# Beacons.net
KiCad netlist of a schematic drawn in Altium Designer
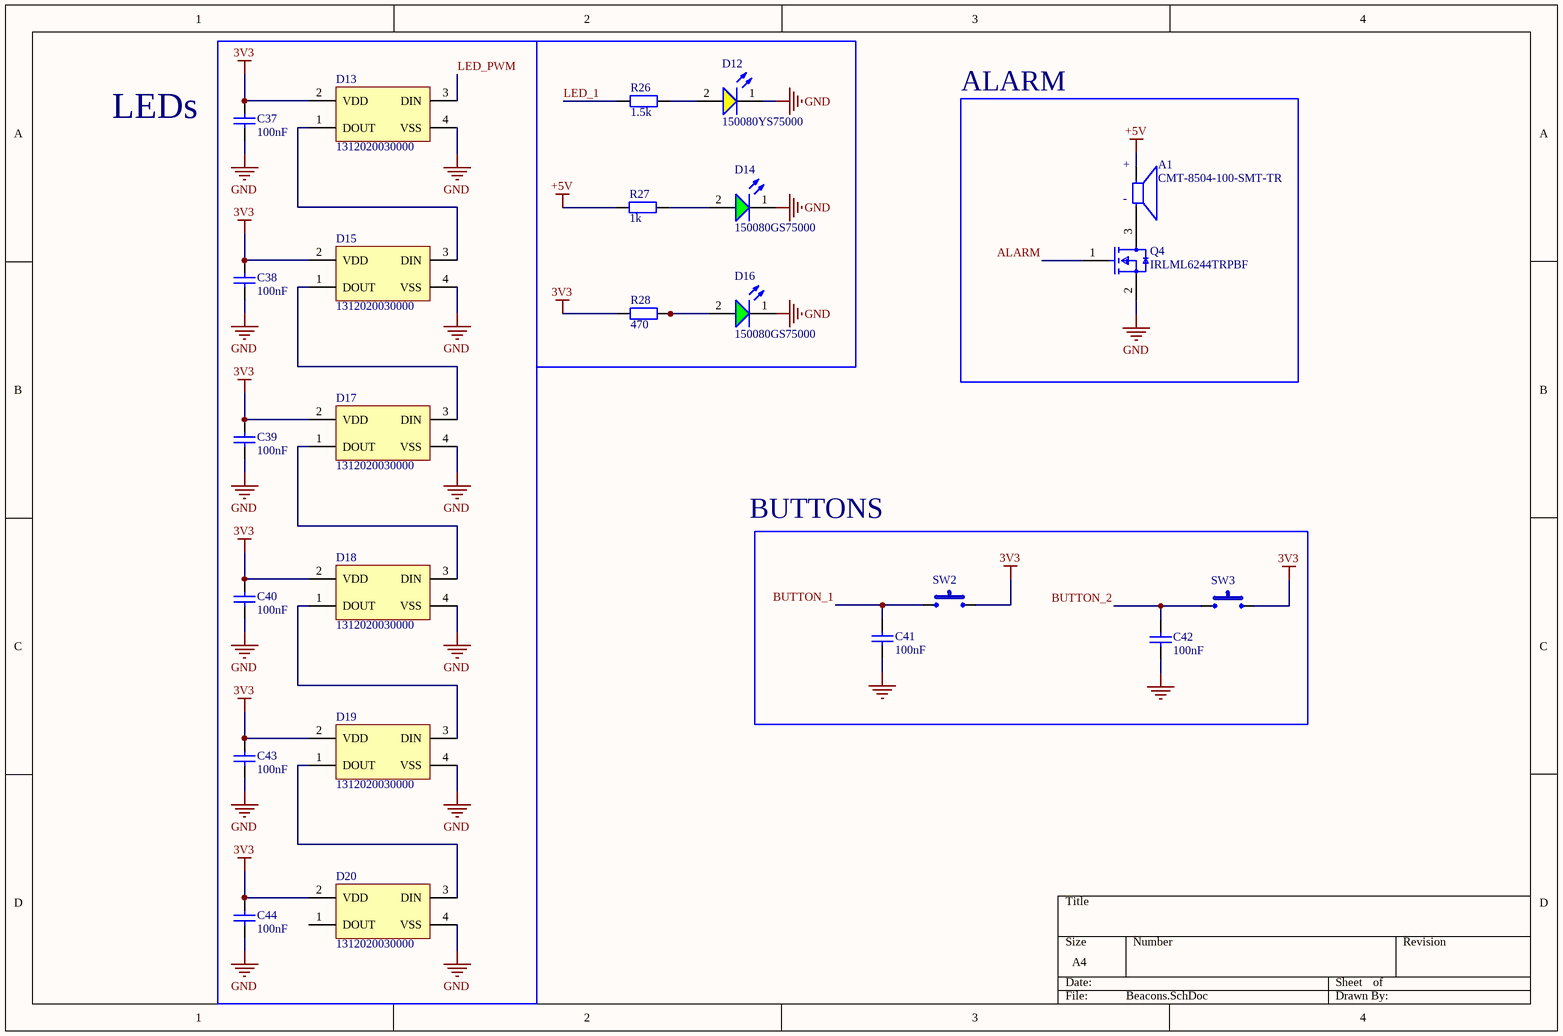
[diagram p0: Beacons.SchDoc]

(export (version "E")
  (design (tool "Eeschema 10.0.6"))
  (components
    (comp (ref "A1")
      (value "CMT-8504-100-SMT-TR")
      (footprint "CMT-8504-100-SMT-TR-Footprint-1")
      (description "Alarm")
      (libsource (lib "LEEM UPM") (part "CMT-8504-100"))
    )
    (comp (ref "C37")
      (value "100nF")
      (footprint "WCAP-CSGP_0603_L1.6W0.8H0.8_Reflow")
      (description "WCAP-CSGP Multilayer Ceramic Chip Capacitor, General Purpose, size 0603, X7R, 100nF, 25VDC")
      (fields
        (field (name "MANUFACTURER") "Wurth Elektronik")
        (field (name "MANUFACTURER PART NUMBER") "885012206071")
      )
      (libsource (lib "LEEM UPM") (part "885012209047R"))
    )
    (comp (ref "C38")
      (value "100nF")
      (footprint "WCAP-CSGP_0603_L1.6W0.8H0.8_Reflow")
      (description "WCAP-CSGP Multilayer Ceramic Chip Capacitor, General Purpose, size 0603, X7R, 100nF, 25VDC")
      (fields
        (field (name "MANUFACTURER") "Wurth Elektronik")
        (field (name "MANUFACTURER PART NUMBER") "885012206071")
      )
      (libsource (lib "LEEM UPM") (part "885012209047R"))
    )
    (comp (ref "C39")
      (value "100nF")
      (footprint "WCAP-CSGP_0603_L1.6W0.8H0.8_Reflow")
      (description "WCAP-CSGP Multilayer Ceramic Chip Capacitor, General Purpose, size 0603, X7R, 100nF, 25VDC")
      (fields
        (field (name "MANUFACTURER") "Wurth Elektronik")
        (field (name "MANUFACTURER PART NUMBER") "885012206071")
      )
      (libsource (lib "LEEM UPM") (part "885012209047R"))
    )
    (comp (ref "C40")
      (value "100nF")
      (footprint "WCAP-CSGP_0603_L1.6W0.8H0.8_Reflow")
      (description "WCAP-CSGP Multilayer Ceramic Chip Capacitor, General Purpose, size 0603, X7R, 100nF, 25VDC")
      (fields
        (field (name "MANUFACTURER") "Wurth Elektronik")
        (field (name "MANUFACTURER PART NUMBER") "885012206071")
      )
      (libsource (lib "LEEM UPM") (part "885012209047R"))
    )
    (comp (ref "C41")
      (value "100nF")
      (footprint "WCAP-CSGP_0603_L1.6W0.8H0.8_Reflow")
      (description "WCAP-CSGP Multilayer Ceramic Chip Capacitor, General Purpose, size 0603, X7R, 100nF, 25VDC")
      (fields
        (field (name "MANUFACTURER") "Wurth Elektronik")
        (field (name "MANUFACTURER PART NUMBER") "885012206071")
      )
      (libsource (lib "LEEM UPM") (part "885012209047R"))
    )
    (comp (ref "C42")
      (value "100nF")
      (footprint "WCAP-CSGP_0603_L1.6W0.8H0.8_Reflow")
      (description "WCAP-CSGP Multilayer Ceramic Chip Capacitor, General Purpose, size 0603, X7R, 100nF, 25VDC")
      (fields
        (field (name "MANUFACTURER") "Wurth Elektronik")
        (field (name "MANUFACTURER PART NUMBER") "885012206071")
      )
      (libsource (lib "LEEM UPM") (part "885012209047R"))
    )
    (comp (ref "C43")
      (value "100nF")
      (footprint "WCAP-CSGP_0603_L1.6W0.8H0.8_Reflow")
      (description "WCAP-CSGP Multilayer Ceramic Chip Capacitor, General Purpose, size 0603, X7R, 100nF, 25VDC")
      (fields
        (field (name "MANUFACTURER") "Wurth Elektronik")
        (field (name "MANUFACTURER PART NUMBER") "885012206071")
      )
      (libsource (lib "LEEM UPM") (part "885012209047R"))
    )
    (comp (ref "C44")
      (value "100nF")
      (footprint "WCAP-CSGP_0603_L1.6W0.8H0.8_Reflow")
      (description "WCAP-CSGP Multilayer Ceramic Chip Capacitor, General Purpose, size 0603, X7R, 100nF, 25VDC")
      (fields
        (field (name "MANUFACTURER") "Wurth Elektronik")
        (field (name "MANUFACTURER PART NUMBER") "885012206071")
      )
      (libsource (lib "LEEM UPM") (part "885012209047R"))
    )
    (comp (ref "D12")
      (value "150080YS75000")
      (footprint "WL-SMCW_0805_150080xx75000")
      (description "WL-SMCW Mono-color Chip LED Waterclear, SMT, size 0805, Yellow, 2V, 140°")
      (fields (field (name "MANUFACTURER") "Wurth Elektronik"))
      (libsource (lib "LEEM UPM") (part "150120YS87000"))
    )
    (comp (ref "D13")
      (value "1312020030000")
      (footprint "1312020030000")
      (description "WL-ICLED Integrated Controller within LED, Chip LED 2020, 5.5mA")
      (fields (field (name "MANUFACTURER") "Wurth Elektronik"))
      (libsource (lib "LEEM UPM") (part "1312020030000"))
    )
    (comp (ref "D14")
      (value "150080GS75000")
      (footprint "WL-SMCW_0805_150080xx75000")
      (description "WL-SMCW Mono-color Chip LED Waterclear, SMT, size 0805, Green, 3.2V, 140°")
      (fields (field (name "MANUFACTURER") "Wurth Elektronik"))
      (libsource (lib "LEEM UPM") (part "150120VS87000"))
    )
    (comp (ref "D15")
      (value "1312020030000")
      (footprint "1312020030000")
      (description "WL-ICLED Integrated Controller within LED, Chip LED 2020, 5.5mA")
      (fields (field (name "MANUFACTURER") "Wurth Elektronik"))
      (libsource (lib "LEEM UPM") (part "1312020030000"))
    )
    (comp (ref "D16")
      (value "150080GS75000")
      (footprint "WL-SMCW_0805_150080xx75000")
      (description "WURTH ELEKTRONIK - 150080GS75000 - LED, Green, SMD, 0805, 30 mA, 3.2 V, 520 nm")
      (libsource (lib "Altium Content Vault") (part "LED_Green_2A-1K"))
    )
    (comp (ref "D17")
      (value "1312020030000")
      (footprint "1312020030000")
      (description "WL-ICLED Integrated Controller within LED, Chip LED 2020, 5.5mA")
      (fields (field (name "MANUFACTURER") "Wurth Elektronik"))
      (libsource (lib "LEEM UPM") (part "1312020030000"))
    )
    (comp (ref "D18")
      (value "1312020030000")
      (footprint "1312020030000")
      (description "WL-ICLED Integrated Controller within LED, Chip LED 2020, 5.5mA")
      (fields (field (name "MANUFACTURER") "Wurth Elektronik"))
      (libsource (lib "LEEM UPM") (part "1312020030000"))
    )
    (comp (ref "D19")
      (value "1312020030000")
      (footprint "1312020030000")
      (description "WL-ICLED Integrated Controller within LED, Chip LED 2020, 5.5mA")
      (fields (field (name "MANUFACTURER") "Wurth Elektronik"))
      (libsource (lib "LEEM UPM") (part "1312020030000"))
    )
    (comp (ref "D20")
      (value "1312020030000")
      (footprint "1312020030000")
      (description "WL-ICLED Integrated Controller within LED, Chip LED 2020, 5.5mA")
      (fields (field (name "MANUFACTURER") "Wurth Elektronik"))
      (libsource (lib "LEEM UPM") (part "1312020030000"))
    )
    (comp (ref "Q4")
      (value "IRLML6244TRPBF")
      (footprint "FP-Micro3-IPC_C")
      (libsource (lib "LEEM UPM") (part "3b9c635fedb024a5347a57b145af9cc"))
    )
    (comp (ref "R26")
      (value "1.5k")
      (footprint "WRIS-RSKS_0603_Reflow")
      (description "WRIS-RSKS Thick Film Resistor, size 0603, 1500Ohm, 100mW")
      (fields
        (field (name "MANUFACTURER") "Wurth Elektronik")
        (field (name "MANUFACTURER PART NUMBER") "560112116038")
      )
      (libsource (lib "LEEM UPM") (part "560112140010"))
    )
    (comp (ref "R27")
      (value "1k")
      (footprint "WRIS-RSKS_0603_Reflow")
      (description "WRIS-RSKS Thick Film Resistor, size 0603, 1000Ohm, 100mW")
      (fields
        (field (name "MANUFACTURER PART NUMBER") "560112116014")
        (field (name "MANUFACTURER") "Wurth Elektronik")
      )
      (libsource (lib "LEEM UPM") (part "560112140010"))
    )
    (comp (ref "R28")
      (value "470")
      (footprint "WRIS-RSKS_0603_Reflow")
      (description "WRIS-RSKS Thick Film Resistor, size 0603, 470Ohm, 100mW")
      (fields
        (field (name "MANUFACTURER") "Wurth Elektronik")
        (field (name "MANUFACTURER PART NUMBER") "560112116067")
      )
      (libsource (lib "") (part "560112140010_1"))
    )
    (comp (ref "SW2")
      (value "PTS815SJM250SMTRLFS")
      (footprint "PTS815SJM250SMTRLFS-Footprint-1")
      (libsource (lib "LEEM UPM") (part "PTS815S"))
    )
    (comp (ref "SW3")
      (value "PTS815SJM250SMTRLFS")
      (footprint "PTS815SJM250SMTRLFS-Footprint-1")
      (libsource (lib "LEEM UPM") (part "PTS815S"))
    )
  )
  (nets
    (net (code "1") (name "+5V") (class "Default")
      (node (ref "A1") (pin "P") (pinfunction "P_P") (pintype "passive"))
      (node (ref "R27") (pin "1") (pinfunction "1_1") (pintype "passive"))
    )
    (net (code "2") (name "/ALARM") (class "Default")
      (node (ref "Q4") (pin "1") (pinfunction "G_1") (pintype "passive"))
    )
    (net (code "3") (name "/BUTTON_1") (class "Default")
      (node (ref "C41") (pin "2") (pinfunction "2_2") (pintype "passive"))
      (node (ref "SW2") (pin "1") (pinfunction "1_1") (pintype "passive"))
    )
    (net (code "4") (name "/BUTTON_2") (class "Default")
      (node (ref "C42") (pin "2") (pinfunction "2_2") (pintype "passive"))
      (node (ref "SW3") (pin "1") (pinfunction "1_1") (pintype "passive"))
    )
    (net (code "5") (name "/LED_1") (class "Default")
      (node (ref "R26") (pin "1") (pinfunction "1_1") (pintype "passive"))
    )
    (net (code "6") (name "/LED_PWM") (class "Default")
      (node (ref "D13") (pin "3") (pinfunction "DIN_3") (pintype "passive"))
    )
    (net (code "7") (name "3V3") (class "Default")
      (node (ref "C37") (pin "2") (pinfunction "2_2") (pintype "passive"))
      (node (ref "C38") (pin "2") (pinfunction "2_2") (pintype "passive"))
      (node (ref "C39") (pin "2") (pinfunction "2_2") (pintype "passive"))
      (node (ref "C40") (pin "2") (pinfunction "2_2") (pintype "passive"))
      (node (ref "C43") (pin "2") (pinfunction "2_2") (pintype "passive"))
      (node (ref "C44") (pin "2") (pinfunction "2_2") (pintype "passive"))
      (node (ref "D13") (pin "2") (pinfunction "VDD_2") (pintype "passive"))
      (node (ref "D15") (pin "2") (pinfunction "VDD_2") (pintype "passive"))
      (node (ref "D17") (pin "2") (pinfunction "VDD_2") (pintype "passive"))
      (node (ref "D18") (pin "2") (pinfunction "VDD_2") (pintype "passive"))
      (node (ref "D19") (pin "2") (pinfunction "VDD_2") (pintype "passive"))
      (node (ref "D20") (pin "2") (pinfunction "VDD_2") (pintype "passive"))
      (node (ref "R28") (pin "2") (pinfunction "2_2") (pintype "passive"))
      (node (ref "SW2") (pin "2") (pinfunction "2_2") (pintype "passive"))
      (node (ref "SW3") (pin "2") (pinfunction "2_2") (pintype "passive"))
    )
    (net (code "8") (name "GND") (class "Default")
      (node (ref "C37") (pin "1") (pinfunction "1_1") (pintype "passive"))
      (node (ref "C38") (pin "1") (pinfunction "1_1") (pintype "passive"))
      (node (ref "C39") (pin "1") (pinfunction "1_1") (pintype "passive"))
      (node (ref "C40") (pin "1") (pinfunction "1_1") (pintype "passive"))
      (node (ref "C41") (pin "1") (pinfunction "1_1") (pintype "passive"))
      (node (ref "C42") (pin "1") (pinfunction "1_1") (pintype "passive"))
      (node (ref "C43") (pin "1") (pinfunction "1_1") (pintype "passive"))
      (node (ref "C44") (pin "1") (pinfunction "1_1") (pintype "passive"))
      (node (ref "D12") (pin "1") (pinfunction "K_1") (pintype "passive"))
      (node (ref "D13") (pin "4") (pinfunction "VSS_4") (pintype "passive"))
      (node (ref "D14") (pin "1") (pinfunction "K_1") (pintype "passive"))
      (node (ref "D15") (pin "4") (pinfunction "VSS_4") (pintype "passive"))
      (node (ref "D16") (pin "1") (pinfunction "K_1") (pintype "passive"))
      (node (ref "D17") (pin "4") (pinfunction "VSS_4") (pintype "passive"))
      (node (ref "D18") (pin "4") (pinfunction "VSS_4") (pintype "passive"))
      (node (ref "D19") (pin "4") (pinfunction "VSS_4") (pintype "passive"))
      (node (ref "D20") (pin "4") (pinfunction "VSS_4") (pintype "passive"))
      (node (ref "Q4") (pin "2") (pinfunction "S_2") (pintype "passive"))
    )
    (net (code "9") (name "Net-(D12-A)") (class "Default")
      (node (ref "D12") (pin "2") (pinfunction "A_2") (pintype "passive"))
      (node (ref "R26") (pin "2") (pinfunction "2_2") (pintype "passive"))
    )
    (net (code "10") (name "Net-(D13-DOUT)") (class "Default")
      (node (ref "D13") (pin "1") (pinfunction "DOUT_1") (pintype "passive"))
      (node (ref "D15") (pin "3") (pinfunction "DIN_3") (pintype "passive"))
    )
    (net (code "11") (name "Net-(D14-A)") (class "Default")
      (node (ref "D14") (pin "2") (pinfunction "A_2") (pintype "passive"))
      (node (ref "R27") (pin "2") (pinfunction "2_2") (pintype "passive"))
    )
    (net (code "12") (name "Net-(D15-DOUT)") (class "Default")
      (node (ref "D15") (pin "1") (pinfunction "DOUT_1") (pintype "passive"))
      (node (ref "D17") (pin "3") (pinfunction "DIN_3") (pintype "passive"))
    )
    (net (code "13") (name "Net-(D16-A)") (class "Default")
      (node (ref "D16") (pin "2") (pinfunction "A_2") (pintype "passive"))
      (node (ref "R28") (pin "1") (pinfunction "1_1") (pintype "passive"))
    )
    (net (code "14") (name "Net-(D17-DOUT)") (class "Default")
      (node (ref "D17") (pin "1") (pinfunction "DOUT_1") (pintype "passive"))
      (node (ref "D18") (pin "3") (pinfunction "DIN_3") (pintype "passive"))
    )
    (net (code "15") (name "Net-(D18-DOUT)") (class "Default")
      (node (ref "D18") (pin "1") (pinfunction "DOUT_1") (pintype "passive"))
      (node (ref "D19") (pin "3") (pinfunction "DIN_3") (pintype "passive"))
    )
    (net (code "16") (name "Net-(D19-DOUT)") (class "Default")
      (node (ref "D19") (pin "1") (pinfunction "DOUT_1") (pintype "passive"))
      (node (ref "D20") (pin "3") (pinfunction "DIN_3") (pintype "passive"))
    )
    (net (code "17") (name "Net-(Q4-D)") (class "Default")
      (node (ref "A1") (pin "N") (pinfunction "N_N") (pintype "passive"))
      (node (ref "Q4") (pin "3") (pinfunction "D_3") (pintype "passive"))
    )
    (net (code "18") (name "unconnected-(D20-DOUT-Pad1)") (class "Default")
      (node (ref "D20") (pin "1") (pinfunction "DOUT_1") (pintype "passive"))
    )
  )
)
